# POWER.net
KiCad netlist of a schematic drawn in Altium Designer
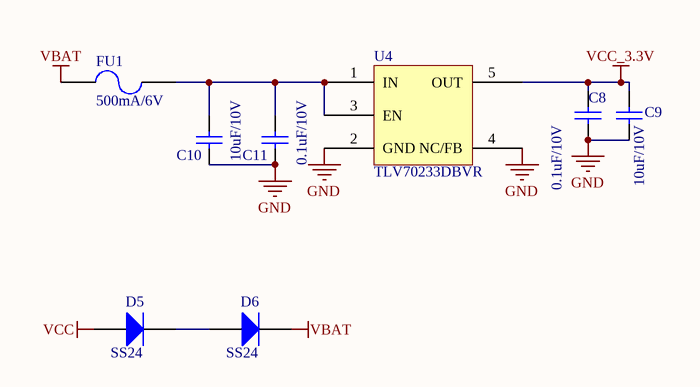
[diagram p0: POWER.SchDoc]

(export (version "E")
  (design (tool "Eeschema 10.0.6"))
  (components
    (comp (ref "C8")
      (value "0.1uF/10V")
      (footprint "0402C")
      (description "Capacitor")
      (fields (field (name "PUBLISHER") "Altium Limited"))
      (libsource (lib "Miscellaneous Devices") (part "Cap"))
    )
    (comp (ref "C9")
      (value "10uF/10V")
      (footprint "0603C")
      (description "Capacitor")
      (fields (field (name "PUBLISHER") "Altium Limited"))
      (libsource (lib "Miscellaneous Devices") (part "Cap"))
    )
    (comp (ref "C10")
      (value "10uF/10V")
      (footprint "0603C")
      (description "Capacitor")
      (fields (field (name "PUBLISHER") "Altium Limited"))
      (libsource (lib "Miscellaneous Devices") (part "Cap"))
    )
    (comp (ref "C11")
      (value "0.1uF/10V")
      (footprint "0402C")
      (description "Capacitor")
      (fields (field (name "PUBLISHER") "Altium Limited"))
      (libsource (lib "Miscellaneous Devices") (part "Cap"))
    )
    (comp (ref "D5")
      (value "SS24")
      (footprint "SMA")
      (description "High Conductance Fast Diode")
      (fields (field (name "PUBLISHER") "Altium Limited"))
      (libsource (lib "Miscellaneous Devices") (part "Diode 1N4148"))
    )
    (comp (ref "D6")
      (value "SS24")
      (footprint "SMA")
      (description "High Conductance Fast Diode")
      (fields (field (name "PUBLISHER") "Altium Limited"))
      (libsource (lib "Miscellaneous Devices") (part "Diode 1N4148"))
    )
    (comp (ref "FU1")
      (value "500mA/6V")
      (footprint "0805R")
      (description "Fuse")
      (libsource (lib "SM") (part "FUSE2"))
    )
    (comp (ref "U4")
      (value "TLV70233DBVR")
      (footprint "SOT23-5(DBV)")
      (libsource (lib "Schlib_20110825") (part "TLV70230DBVR"))
    )
  )
  (nets
    (net (code "1") (name "GND") (class "Default")
      (node (ref "C10") (pin "1") (pinfunction "1_1") (pintype "passive"))
      (node (ref "C11") (pin "2") (pinfunction "2_2") (pintype "passive"))
      (node (ref "C8") (pin "2") (pinfunction "2_2") (pintype "passive"))
      (node (ref "C9") (pin "1") (pinfunction "1_1") (pintype "passive"))
      (node (ref "U4") (pin "2") (pinfunction "GND_2") (pintype "passive"))
      (node (ref "U4") (pin "4") (pinfunction "NC/FB_4") (pintype "passive"))
    )
    (net (code "2") (name "Net-(D5-K)") (class "Default")
      (node (ref "D5") (pin "2") (pinfunction "K_2") (pintype "passive"))
      (node (ref "D6") (pin "1") (pinfunction "A_1") (pintype "passive"))
    )
    (net (code "3") (name "Net-(U4-EN)") (class "Default")
      (node (ref "C10") (pin "2") (pinfunction "2_2") (pintype "passive"))
      (node (ref "C11") (pin "1") (pinfunction "1_1") (pintype "passive"))
      (node (ref "FU1") (pin "2") (pinfunction "2_2") (pintype "passive"))
      (node (ref "U4") (pin "1") (pinfunction "IN_1") (pintype "passive"))
      (node (ref "U4") (pin "3") (pinfunction "EN_3") (pintype "passive"))
    )
    (net (code "4") (name "VBAT") (class "Default")
      (node (ref "D6") (pin "2") (pinfunction "K_2") (pintype "passive"))
      (node (ref "FU1") (pin "1") (pinfunction "1_1") (pintype "passive"))
    )
    (net (code "5") (name "VCC") (class "Default")
      (node (ref "D5") (pin "1") (pinfunction "A_1") (pintype "passive"))
    )
    (net (code "6") (name "VCC_3.3V") (class "Default")
      (node (ref "C8") (pin "1") (pinfunction "1_1") (pintype "passive"))
      (node (ref "C9") (pin "2") (pinfunction "2_2") (pintype "passive"))
      (node (ref "U4") (pin "5") (pinfunction "OUT_5") (pintype "passive"))
    )
  )
)
